# PCB.net
KiCad netlist of a schematic drawn in EAGLE
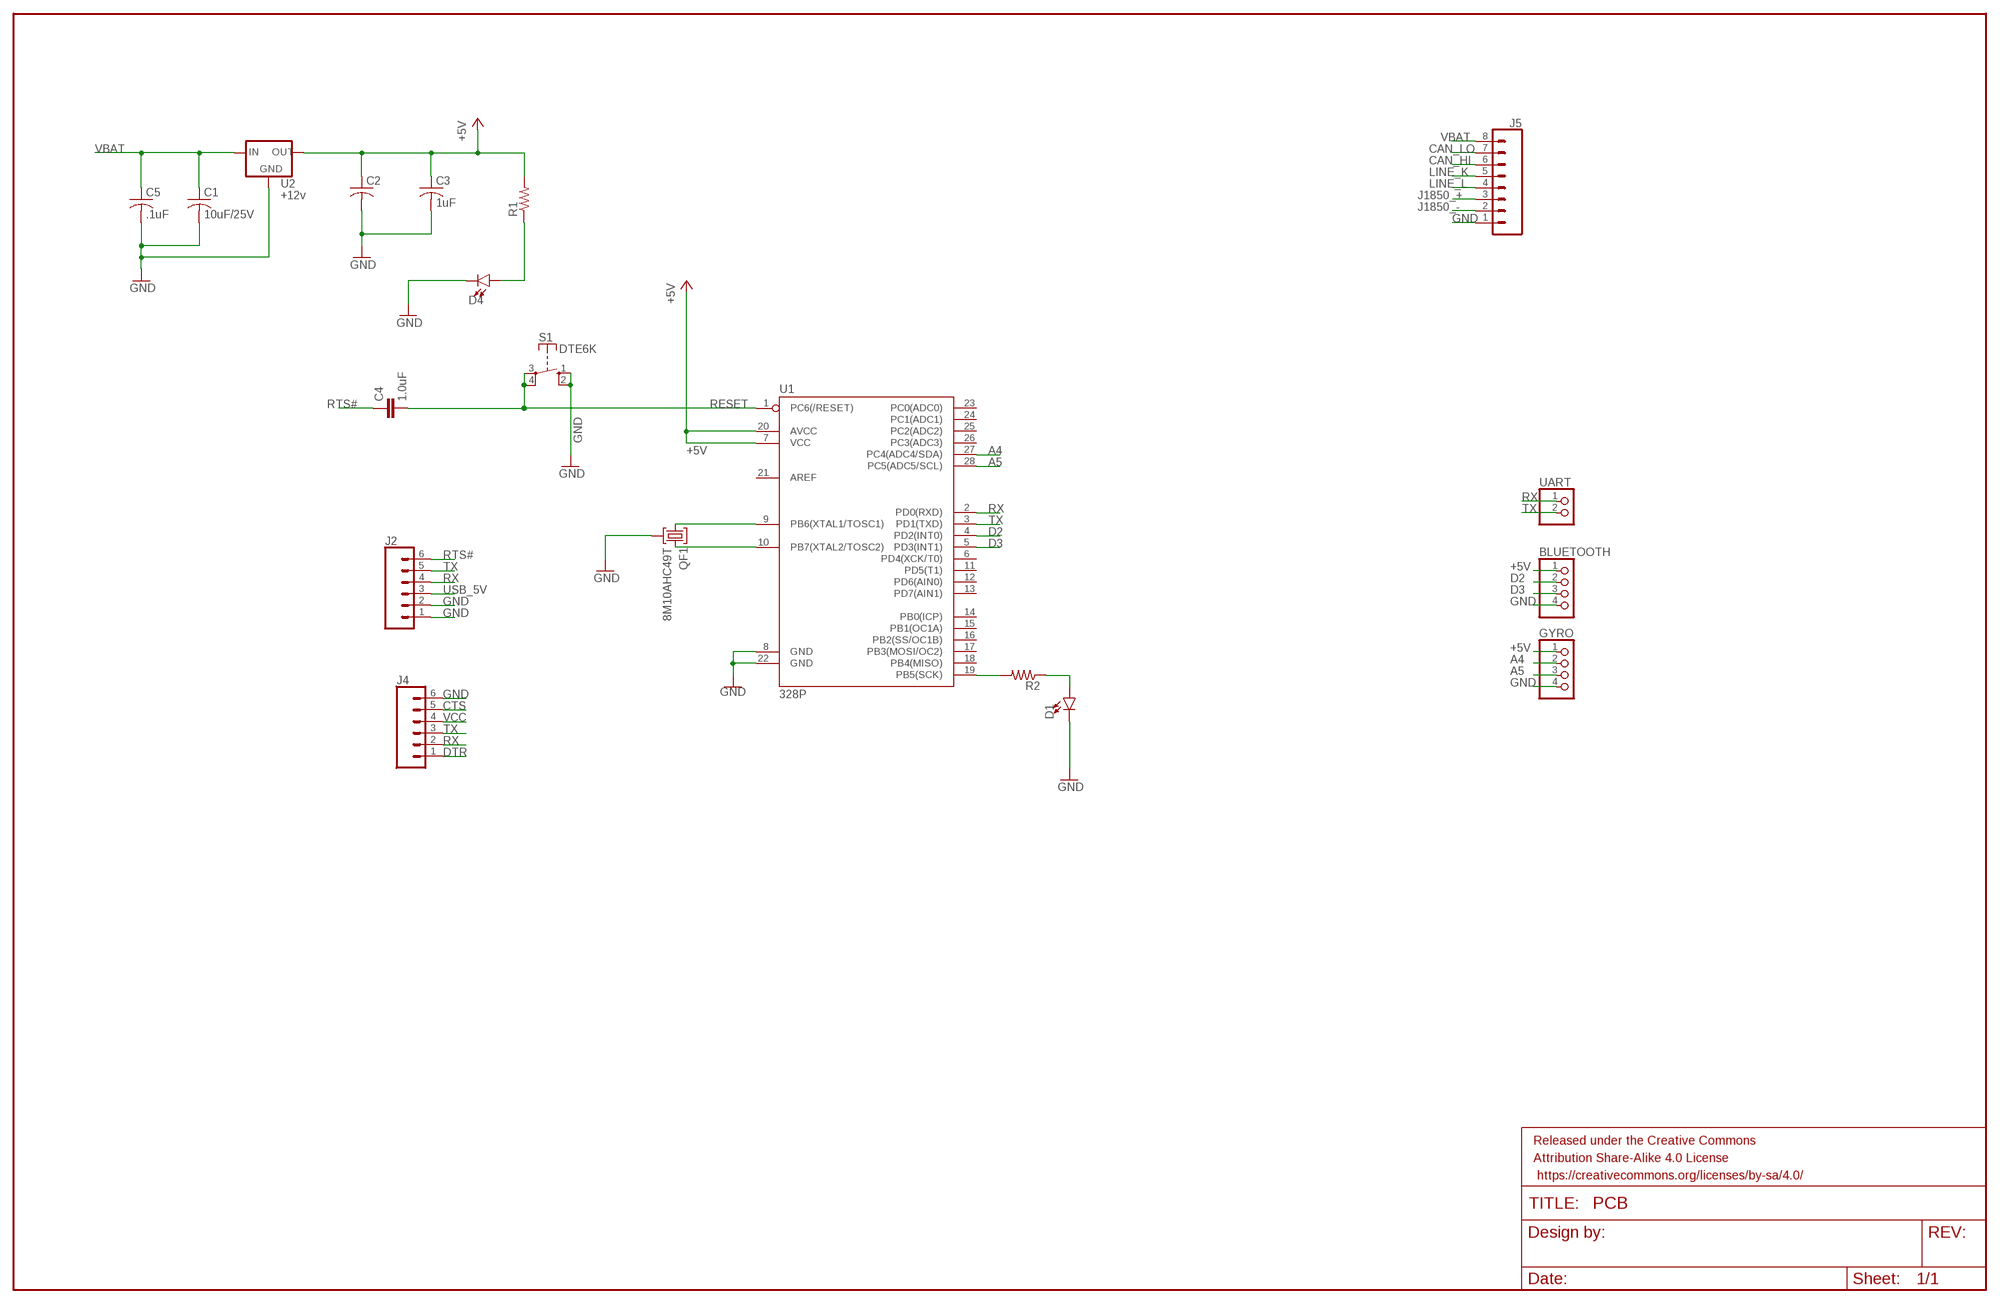
[diagram p0: schematic, sheet 1]

(export (version "E")
  (design (tool "Eeschema 10.0.6"))
  (components
    (comp (ref "BLUETOOTH")
      (value "PINHD-1X4")
      (footprint "eagle-import:1X04")
      (libsource (lib "eagle-import") (part "PINHD-1X4"))
    )
    (comp (ref "C1")
      (value "10uF/25V")
      (footprint "eagle-import:C050-025X075")
      (libsource (lib "eagle-import") (part "C-US050-025X075"))
    )
    (comp (ref "C2")
      (value "C-US050-025X075")
      (footprint "eagle-import:C050-025X075")
      (libsource (lib "eagle-import") (part "C-US050-025X075"))
    )
    (comp (ref "C3")
      (value "1uF")
      (footprint "eagle-import:C050-025X075")
      (libsource (lib "eagle-import") (part "C-US050-025X075"))
    )
    (comp (ref "C4")
      (value "1.0uF")
      (footprint "eagle-import:1206")
      (libsource (lib "eagle-import") (part "1.0UF-1206-50V-10%"))
    )
    (comp (ref "C5")
      (value ".1uF")
      (footprint "eagle-import:C050-025X075")
      (libsource (lib "eagle-import") (part "C-US050-025X075"))
    )
    (comp (ref "D1")
      (value "LED3MM")
      (footprint "eagle-import:LED_3MM")
      (libsource (lib "eagle-import") (part "LED3MM"))
    )
    (comp (ref "D4")
      (value "LED3MM")
      (footprint "eagle-import:LED_3MM")
      (libsource (lib "eagle-import") (part "LED3MM"))
    )
    (comp (ref "FRAME1")
      (value "FRAME-LEDGER")
      (footprint "eagle-import:CREATIVE_COMMONS")
      (libsource (lib "eagle-import") (part "FRAME-LEDGER"))
    )
    (comp (ref "GYRO")
      (value "PINHD-1X4")
      (footprint "eagle-import:1X04")
      (libsource (lib "eagle-import") (part "PINHD-1X4"))
    )
    (comp (ref "J2")
      (value "CONN_06LONGPADS")
      (footprint "eagle-import:1X06_LONGPADS")
      (libsource (lib "eagle-import") (part "CONN_06LONGPADS"))
    )
    (comp (ref "J4")
      (value "CONN_06LONGPADS")
      (footprint "eagle-import:1X06_LONGPADS")
      (libsource (lib "eagle-import") (part "CONN_06LONGPADS"))
    )
    (comp (ref "J5")
      (value "CONN_08LONGPADS")
      (footprint "eagle-import:1X08_LONGPADS")
      (libsource (lib "eagle-import") (part "CONN_08LONGPADS"))
    )
    (comp (ref "QF1")
      (value "8M10AHC49T")
      (footprint "eagle-import:HC49U")
      (libsource (lib "eagle-import") (part "8M10AHC49T"))
    )
    (comp (ref "R1")
      (value "R-US_0204/5")
      (footprint "eagle-import:0204_5")
      (libsource (lib "eagle-import") (part "R-US_0204/5"))
    )
    (comp (ref "R2")
      (value "R-US_0204/5")
      (footprint "eagle-import:0204_5")
      (libsource (lib "eagle-import") (part "R-US_0204/5"))
    )
    (comp (ref "S1")
      (value "DTE6K")
      (footprint "eagle-import:DTE6K")
      (libsource (lib "eagle-import") (part "DTE6K"))
    )
    (comp (ref "U1")
      (value "328P")
      (footprint "eagle-import:DIP28")
      (libsource (lib "eagle-import") (part "ATMEGA328P_PDIP"))
    )
    (comp (ref "U2")
      (value "+12v")
      (footprint "eagle-import:TO-252")
      (libsource (lib "eagle-import") (part "V_REG_78XX7812"))
    )
    (comp (ref "UART")
      (value "PINHD-1X2")
      (footprint "eagle-import:1X02")
      (libsource (lib "eagle-import") (part "PINHD-1X2"))
    )
  )
  (nets
    (net (code "1") (name "+5V") (class "Default")
      (node (ref "BLUETOOTH") (pin "1") (pinfunction "1_1") (pintype "passive"))
      (node (ref "C2") (pin "1") (pinfunction "1_1") (pintype "passive"))
      (node (ref "C3") (pin "1") (pinfunction "1_1") (pintype "passive"))
      (node (ref "GYRO") (pin "1") (pinfunction "1_1") (pintype "passive"))
      (node (ref "R1") (pin "2") (pinfunction "2_2") (pintype "passive"))
      (node (ref "U1") (pin "20") (pinfunction "AVCC_20") (pintype "bidirectional"))
      (node (ref "U1") (pin "7") (pinfunction "VCC_7") (pintype "bidirectional"))
      (node (ref "U2") (pin "2") (pinfunction "OUT_2") (pintype "passive"))
    )
    (net (code "2") (name "/A4") (class "Default")
      (node (ref "GYRO") (pin "2") (pinfunction "2_2") (pintype "passive"))
      (node (ref "U1") (pin "27") (pinfunction "PC4(ADC4/SDA)_27") (pintype "bidirectional"))
    )
    (net (code "3") (name "/A5") (class "Default")
      (node (ref "GYRO") (pin "3") (pinfunction "3_3") (pintype "passive"))
      (node (ref "U1") (pin "28") (pinfunction "PC5(ADC5/SCL)_28") (pintype "bidirectional"))
    )
    (net (code "4") (name "/CAN_HI") (class "Default")
      (node (ref "J5") (pin "6") (pinfunction "6_6") (pintype "passive"))
    )
    (net (code "5") (name "/CAN_LO") (class "Default")
      (node (ref "J5") (pin "7") (pinfunction "7_7") (pintype "passive"))
    )
    (net (code "6") (name "/CTS") (class "Default")
      (node (ref "J4") (pin "5") (pinfunction "5_5") (pintype "passive"))
    )
    (net (code "7") (name "/D2") (class "Default")
      (node (ref "BLUETOOTH") (pin "2") (pinfunction "2_2") (pintype "passive"))
      (node (ref "U1") (pin "4") (pinfunction "PD2(INT0)_4") (pintype "bidirectional"))
    )
    (net (code "8") (name "/D3") (class "Default")
      (node (ref "BLUETOOTH") (pin "3") (pinfunction "3_3") (pintype "passive"))
      (node (ref "U1") (pin "5") (pinfunction "PD3(INT1)_5") (pintype "bidirectional"))
    )
    (net (code "9") (name "/DTR") (class "Default")
      (node (ref "J4") (pin "1") (pinfunction "1_1") (pintype "passive"))
    )
    (net (code "10") (name "/J1850_+") (class "Default")
      (node (ref "J5") (pin "3") (pinfunction "3_3") (pintype "passive"))
    )
    (net (code "11") (name "/J1850_-") (class "Default")
      (node (ref "J5") (pin "2") (pinfunction "2_2") (pintype "passive"))
    )
    (net (code "12") (name "/LINE_K") (class "Default")
      (node (ref "J5") (pin "5") (pinfunction "5_5") (pintype "passive"))
    )
    (net (code "13") (name "/LINE_L") (class "Default")
      (node (ref "J5") (pin "4") (pinfunction "4_4") (pintype "passive"))
    )
    (net (code "14") (name "/RESET") (class "Default")
      (node (ref "C4") (pin "2") (pinfunction "2_2") (pintype "passive"))
      (node (ref "S1") (pin "3") (pinfunction "P_3") (pintype "passive"))
      (node (ref "S1") (pin "4") (pinfunction "P_4") (pintype "passive"))
      (node (ref "U1") (pin "1") (pinfunction "PC6(/RESET)_1") (pintype "bidirectional"))
    )
    (net (code "15") (name "/RTS#") (class "Default")
      (node (ref "C4") (pin "1") (pinfunction "1_1") (pintype "passive"))
      (node (ref "J2") (pin "6") (pinfunction "6_6") (pintype "passive"))
    )
    (net (code "16") (name "/RX") (class "Default")
      (node (ref "J2") (pin "4") (pinfunction "4_4") (pintype "passive"))
      (node (ref "J4") (pin "2") (pinfunction "2_2") (pintype "passive"))
      (node (ref "U1") (pin "2") (pinfunction "PD0(RXD)_2") (pintype "bidirectional"))
      (node (ref "UART") (pin "1") (pinfunction "1_1") (pintype "passive"))
    )
    (net (code "17") (name "/TX") (class "Default")
      (node (ref "J2") (pin "5") (pinfunction "5_5") (pintype "passive"))
      (node (ref "J4") (pin "3") (pinfunction "3_3") (pintype "passive"))
      (node (ref "U1") (pin "3") (pinfunction "PD1(TXD)_3") (pintype "bidirectional"))
      (node (ref "UART") (pin "2") (pinfunction "2_2") (pintype "passive"))
    )
    (net (code "18") (name "/USB_5V") (class "Default")
      (node (ref "J2") (pin "3") (pinfunction "3_3") (pintype "passive"))
    )
    (net (code "19") (name "/VBAT") (class "Default")
      (node (ref "C1") (pin "1") (pinfunction "1_1") (pintype "passive"))
      (node (ref "C5") (pin "1") (pinfunction "1_1") (pintype "passive"))
      (node (ref "J5") (pin "8") (pinfunction "8_8") (pintype "passive"))
      (node (ref "U2") (pin "1") (pinfunction "IN_1") (pintype "input"))
    )
    (net (code "20") (name "/VCC") (class "Default")
      (node (ref "J4") (pin "4") (pinfunction "4_4") (pintype "passive"))
    )
    (net (code "21") (name "GND") (class "Default")
      (node (ref "BLUETOOTH") (pin "4") (pinfunction "4_4") (pintype "passive"))
      (node (ref "C1") (pin "2") (pinfunction "2_2") (pintype "passive"))
      (node (ref "C2") (pin "2") (pinfunction "2_2") (pintype "passive"))
      (node (ref "C3") (pin "2") (pinfunction "2_2") (pintype "passive"))
      (node (ref "C5") (pin "2") (pinfunction "2_2") (pintype "passive"))
      (node (ref "D1") (pin "K") (pinfunction "C_K") (pintype "passive"))
      (node (ref "D4") (pin "K") (pinfunction "C_K") (pintype "passive"))
      (node (ref "GYRO") (pin "4") (pinfunction "4_4") (pintype "passive"))
      (node (ref "J2") (pin "1") (pinfunction "1_1") (pintype "passive"))
      (node (ref "J2") (pin "2") (pinfunction "2_2") (pintype "passive"))
      (node (ref "J4") (pin "6") (pinfunction "6_6") (pintype "passive"))
      (node (ref "J5") (pin "1") (pinfunction "1_1") (pintype "passive"))
      (node (ref "QF1") (pin "2") (pinfunction "2_2") (pintype "passive"))
      (node (ref "S1") (pin "1") (pinfunction "S_1") (pintype "passive"))
      (node (ref "S1") (pin "2") (pinfunction "S_2") (pintype "passive"))
      (node (ref "U1") (pin "22") (pinfunction "GND_22") (pintype "bidirectional"))
      (node (ref "U1") (pin "8") (pinfunction "GND_8") (pintype "bidirectional"))
      (node (ref "U2") (pin "3") (pinfunction "GND_3") (pintype "input"))
    )
    (net (code "22") (name "Net-(D1-PadA)") (class "Default")
      (node (ref "D1") (pin "A") (pinfunction "A_A") (pintype "passive"))
      (node (ref "R2") (pin "1") (pinfunction "1_1") (pintype "passive"))
    )
    (net (code "23") (name "Net-(D4-PadA)") (class "Default")
      (node (ref "D4") (pin "A") (pinfunction "A_A") (pintype "passive"))
      (node (ref "R1") (pin "1") (pinfunction "1_1") (pintype "passive"))
    )
    (net (code "24") (name "Net-(U1-PB5(SCK))") (class "Default")
      (node (ref "R2") (pin "2") (pinfunction "2_2") (pintype "passive"))
      (node (ref "U1") (pin "19") (pinfunction "PB5(SCK)_19") (pintype "bidirectional"))
    )
    (net (code "25") (name "Net-(U1-PB6(XTAL1{slash}TOSC1))") (class "Default")
      (node (ref "QF1") (pin "1") (pinfunction "1_1") (pintype "passive"))
      (node (ref "U1") (pin "9") (pinfunction "PB6(XTAL1/TOSC1)_9") (pintype "bidirectional"))
    )
    (net (code "26") (name "Net-(U1-PB7(XTAL2{slash}TOSC2))") (class "Default")
      (node (ref "QF1") (pin "3") (pinfunction "3_3") (pintype "passive"))
      (node (ref "U1") (pin "10") (pinfunction "PB7(XTAL2/TOSC2)_10") (pintype "bidirectional"))
    )
    (net (code "27") (name "unconnected-(U1-AREF-Pad21)") (class "Default")
      (node (ref "U1") (pin "21") (pinfunction "AREF_21") (pintype "bidirectional"))
    )
    (net (code "28") (name "unconnected-(U1-PB0(ICP)-Pad14)") (class "Default")
      (node (ref "U1") (pin "14") (pinfunction "PB0(ICP)_14") (pintype "bidirectional"))
    )
    (net (code "29") (name "unconnected-(U1-PB1(OC1A)-Pad15)") (class "Default")
      (node (ref "U1") (pin "15") (pinfunction "PB1(OC1A)_15") (pintype "bidirectional"))
    )
    (net (code "30") (name "unconnected-(U1-PB2(SS{slash}OC1B)-Pad16)") (class "Default")
      (node (ref "U1") (pin "16") (pinfunction "PB2(SS/OC1B)_16") (pintype "bidirectional"))
    )
    (net (code "31") (name "unconnected-(U1-PB3(MOSI{slash}OC2)-Pad17)") (class "Default")
      (node (ref "U1") (pin "17") (pinfunction "PB3(MOSI/OC2)_17") (pintype "bidirectional"))
    )
    (net (code "32") (name "unconnected-(U1-PB4(MISO)-Pad18)") (class "Default")
      (node (ref "U1") (pin "18") (pinfunction "PB4(MISO)_18") (pintype "bidirectional"))
    )
    (net (code "33") (name "unconnected-(U1-PC0(ADC0)-Pad23)") (class "Default")
      (node (ref "U1") (pin "23") (pinfunction "PC0(ADC0)_23") (pintype "bidirectional"))
    )
    (net (code "34") (name "unconnected-(U1-PC1(ADC1)-Pad24)") (class "Default")
      (node (ref "U1") (pin "24") (pinfunction "PC1(ADC1)_24") (pintype "bidirectional"))
    )
    (net (code "35") (name "unconnected-(U1-PC2(ADC2)-Pad25)") (class "Default")
      (node (ref "U1") (pin "25") (pinfunction "PC2(ADC2)_25") (pintype "bidirectional"))
    )
    (net (code "36") (name "unconnected-(U1-PC3(ADC3)-Pad26)") (class "Default")
      (node (ref "U1") (pin "26") (pinfunction "PC3(ADC3)_26") (pintype "bidirectional"))
    )
    (net (code "37") (name "unconnected-(U1-PD4(XCK{slash}T0)-Pad6)") (class "Default")
      (node (ref "U1") (pin "6") (pinfunction "PD4(XCK/T0)_6") (pintype "bidirectional"))
    )
    (net (code "38") (name "unconnected-(U1-PD5(T1)-Pad11)") (class "Default")
      (node (ref "U1") (pin "11") (pinfunction "PD5(T1)_11") (pintype "bidirectional"))
    )
    (net (code "39") (name "unconnected-(U1-PD6(AIN0)-Pad12)") (class "Default")
      (node (ref "U1") (pin "12") (pinfunction "PD6(AIN0)_12") (pintype "bidirectional"))
    )
    (net (code "40") (name "unconnected-(U1-PD7(AIN1)-Pad13)") (class "Default")
      (node (ref "U1") (pin "13") (pinfunction "PD7(AIN1)_13") (pintype "bidirectional"))
    )
  )
)
